# Retrolite_CM4_-_Right_PCB.net
KiCad netlist of a schematic drawn in EAGLE
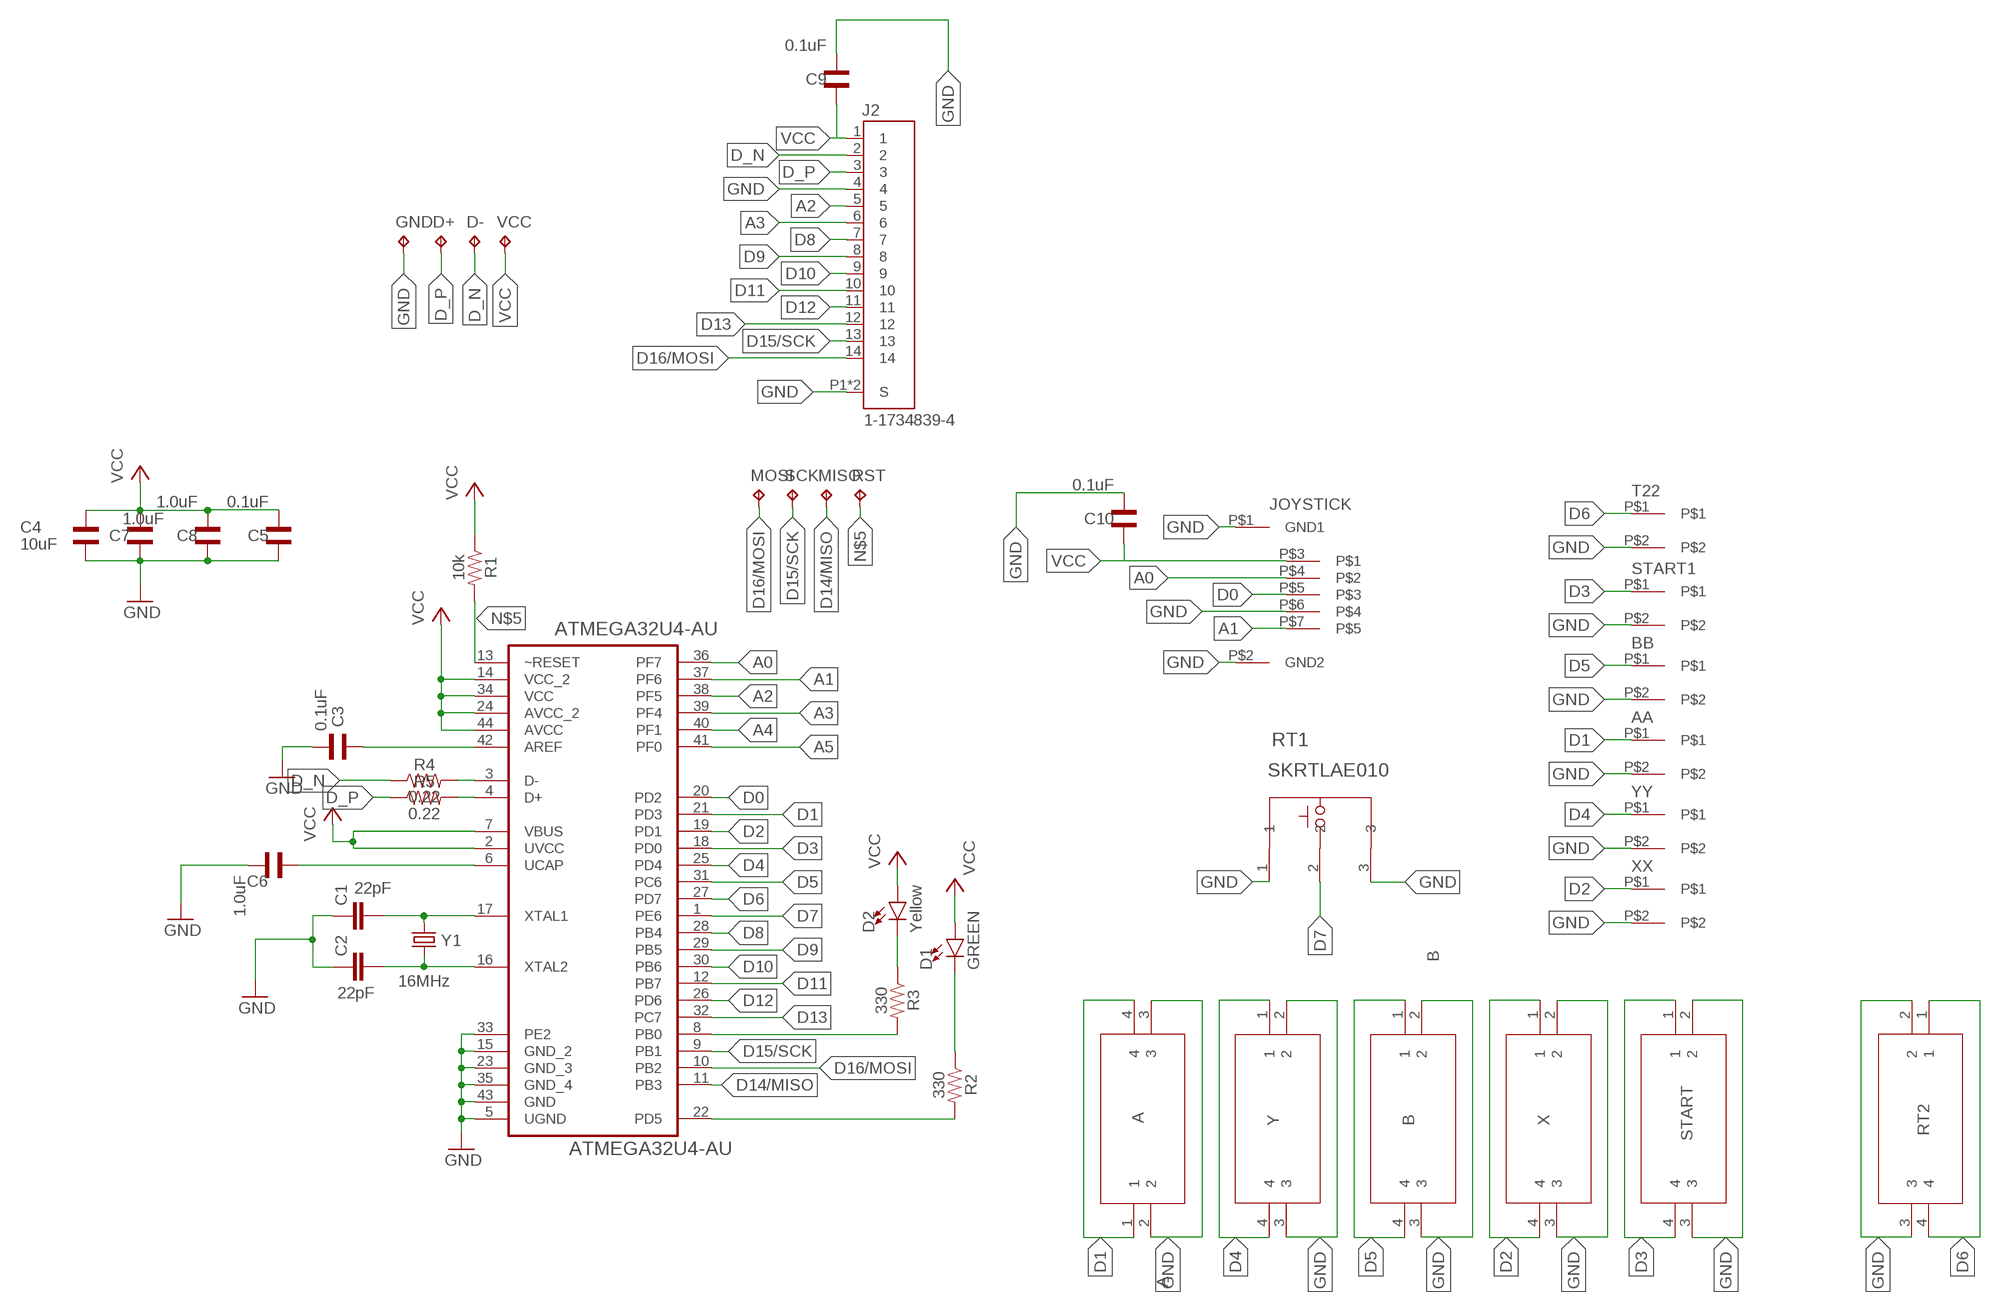
[diagram p0: schematic, sheet 1]

(export (version "E")
  (design (tool "Eeschema 10.0.6"))
  (components
    (comp (ref "A")
      (value "A")
      (footprint "eagle-import:EVQQ2_3")
      (fields (field (name "MF") "Panasonic Electronic") (field (name "MP") "EVQQ2B03W"))
      (libsource (lib "eagle-import") (part "EVQ-Q2B03W"))
    )
    (comp (ref "AA")
      (value "MEMBRANEBUTTON")
      (footprint "eagle-import:MEMBRANEBUTTON")
      (libsource (lib "eagle-import") (part "MEMBRANEBUTTON"))
    )
    (comp (ref "ATMEGA32U4-AU")
      (value "ATMEGA32U4-AU")
      (footprint "eagle-import:QFP80P1200X1200X120-44N")
      (fields (field (name "MF") "Microchip Technology"))
      (libsource (lib "eagle-import") (part "ATMEGA32U4-AU"))
    )
    (comp (ref "B")
      (value "B")
      (footprint "eagle-import:EVQQ2_3")
      (fields (field (name "MF") "Panasonic Electronic") (field (name "MP") "EVQQ2B03W"))
      (libsource (lib "eagle-import") (part "EVQ-Q2B03W"))
    )
    (comp (ref "BB")
      (value "MEMBRANEBUTTON")
      (footprint "eagle-import:MEMBRANEBUTTON")
      (libsource (lib "eagle-import") (part "MEMBRANEBUTTON"))
    )
    (comp (ref "C1")
      (value "22pF")
      (footprint "eagle-import:0603")
      (libsource (lib "eagle-import") (part "22PF-0603-50V-5%"))
    )
    (comp (ref "C2")
      (value "22pF")
      (footprint "eagle-import:0603")
      (libsource (lib "eagle-import") (part "22PF-0603-50V-5%"))
    )
    (comp (ref "C3")
      (value "0.1uF")
      (footprint "eagle-import:WCAP-CSGP_0805_WAVE")
      (libsource (lib "eagle-import") (part "WCAP-CSGP_0805_WAVE_885012006018"))
    )
    (comp (ref "C4")
      (value "10uF")
      (footprint "eagle-import:WCAP-CSGP_0805_WAVE")
      (libsource (lib "eagle-import") (part "WCAP-CSGP_0805_WAVE_885012006018"))
    )
    (comp (ref "C5")
      (value "0.1uF")
      (footprint "eagle-import:WCAP-CSGP_0805_WAVE")
      (libsource (lib "eagle-import") (part "WCAP-CSGP_0805_WAVE_885012006018"))
    )
    (comp (ref "C6")
      (value "1.0uF")
      (footprint "eagle-import:WCAP-CSGP_0805_WAVE")
      (libsource (lib "eagle-import") (part "WCAP-CSGP_0805_WAVE_885012006018"))
    )
    (comp (ref "C7")
      (value "1.0uF")
      (footprint "eagle-import:WCAP-CSGP_0805_WAVE")
      (libsource (lib "eagle-import") (part "WCAP-CSGP_0805_WAVE_885012006018"))
    )
    (comp (ref "C8")
      (value "1.0uF")
      (footprint "eagle-import:WCAP-CSGP_0805_WAVE")
      (libsource (lib "eagle-import") (part "WCAP-CSGP_0805_WAVE_885012006018"))
    )
    (comp (ref "C9")
      (value "0.1uF")
      (footprint "eagle-import:WCAP-CSGP_0805_WAVE")
      (libsource (lib "eagle-import") (part "WCAP-CSGP_0805_WAVE_885012006018"))
    )
    (comp (ref "C10")
      (value "0.1uF")
      (footprint "eagle-import:WCAP-CSGP_0805_WAVE")
      (libsource (lib "eagle-import") (part "WCAP-CSGP_0805_WAVE_885012006018"))
    )
    (comp (ref "D+")
      (value "TPB1,27")
      (footprint "eagle-import:B1,27")
      (libsource (lib "eagle-import") (part "TPB1,27"))
    )
    (comp (ref "D-")
      (value "TPB1,27")
      (footprint "eagle-import:B1,27")
      (libsource (lib "eagle-import") (part "TPB1,27"))
    )
    (comp (ref "D1")
      (value "GREEN")
      (footprint "eagle-import:LED-0603")
      (libsource (lib "eagle-import") (part "LED-GREEN0603"))
    )
    (comp (ref "D2")
      (value "Yellow")
      (footprint "eagle-import:LED-0603")
      (libsource (lib "eagle-import") (part "LED-YELLOW0603"))
    )
    (comp (ref "GND")
      (value "TPB1,27")
      (footprint "eagle-import:B1,27")
      (libsource (lib "eagle-import") (part "TPB1,27"))
    )
    (comp (ref "J2")
      (value "1-1734839-4")
      (footprint "eagle-import:TE_1-1734839-4")
      (fields (field (name "DIGI-KEY_PART_NUMBER") "A100295CT-ND") (field (name "MF") "TE Connectivity"))
      (libsource (lib "eagle-import") (part "1-1734839-4"))
    )
    (comp (ref "JOYSTICK")
      (value "0545500571")
      (footprint "eagle-import:0545500571")
      (libsource (lib "eagle-import") (part "0545500571"))
    )
    (comp (ref "MISO")
      (value "TPB1,27")
      (footprint "eagle-import:B1,27")
      (libsource (lib "eagle-import") (part "TPB1,27"))
    )
    (comp (ref "MOSI")
      (value "TPB1,27")
      (footprint "eagle-import:B1,27")
      (libsource (lib "eagle-import") (part "TPB1,27"))
    )
    (comp (ref "R1")
      (value "10k")
      (footprint "eagle-import:0603")
      (libsource (lib "eagle-import") (part "10KOHM-0603-1/10W-1%"))
    )
    (comp (ref "R2")
      (value "330")
      (footprint "eagle-import:0603")
      (libsource (lib "eagle-import") (part "1.6KOHM-0603-1/10W-1%"))
    )
    (comp (ref "R3")
      (value "330")
      (footprint "eagle-import:0603")
      (libsource (lib "eagle-import") (part "1.6KOHM-0603-1/10W-1%"))
    )
    (comp (ref "R4")
      (value "0.22")
      (footprint "eagle-import:0805")
      (libsource (lib "eagle-import") (part "0.22OHM-0805-1/4W-1%"))
    )
    (comp (ref "R5")
      (value "0.22")
      (footprint "eagle-import:0805")
      (libsource (lib "eagle-import") (part "0.22OHM-0805-1/4W-1%"))
    )
    (comp (ref "RST")
      (value "TPB1,27")
      (footprint "eagle-import:B1,27")
      (libsource (lib "eagle-import") (part "TPB1,27"))
    )
    (comp (ref "RT1")
      (value "SKRTLAE010")
      (footprint "eagle-import:SW3_SKRTLAE010_ALPS")
      (fields (field (name "COPYRIGHT") "Copyright (C) 2016 Accelerated Designs. All rights reserved"))
      (libsource (lib "eagle-import") (part "SKRTLAE010"))
    )
    (comp (ref "RT2")
      (value "T2")
      (footprint "eagle-import:EVQQ2_3")
      (fields (field (name "MF") "Panasonic Electronic") (field (name "MP") "EVQQ2B03W"))
      (libsource (lib "eagle-import") (part "EVQ-Q2B03W"))
    )
    (comp (ref "SCK")
      (value "TPB1,27")
      (footprint "eagle-import:B1,27")
      (libsource (lib "eagle-import") (part "TPB1,27"))
    )
    (comp (ref "START")
      (value "START")
      (footprint "eagle-import:EVQQ2_3")
      (fields (field (name "MF") "Panasonic Electronic") (field (name "MP") "EVQQ2B03W"))
      (libsource (lib "eagle-import") (part "EVQ-Q2B03W"))
    )
    (comp (ref "START1")
      (value "MEMBRANEBUTTON")
      (footprint "eagle-import:MEMBRANEBUTTON")
      (libsource (lib "eagle-import") (part "MEMBRANEBUTTON"))
    )
    (comp (ref "T22")
      (value "MEMBRANEBUTTON")
      (footprint "eagle-import:MEMBRANEBUTTON")
      (libsource (lib "eagle-import") (part "MEMBRANEBUTTON"))
    )
    (comp (ref "VCC")
      (value "TPB1,27")
      (footprint "eagle-import:B1,27")
      (libsource (lib "eagle-import") (part "TPB1,27"))
    )
    (comp (ref "X")
      (value "X")
      (footprint "eagle-import:EVQQ2_3")
      (fields (field (name "MF") "Panasonic Electronic") (field (name "MP") "EVQQ2B03W"))
      (libsource (lib "eagle-import") (part "EVQ-Q2B03W"))
    )
    (comp (ref "XX")
      (value "MEMBRANEBUTTON")
      (footprint "eagle-import:MEMBRANEBUTTON")
      (libsource (lib "eagle-import") (part "MEMBRANEBUTTON"))
    )
    (comp (ref "Y")
      (value "Y")
      (footprint "eagle-import:EVQQ2_3")
      (fields (field (name "MF") "Panasonic Electronic") (field (name "MP") "EVQQ2B03W"))
      (libsource (lib "eagle-import") (part "EVQ-Q2B03W"))
    )
    (comp (ref "Y1")
      (value "16MHz")
      (footprint "eagle-import:CRYSTAL-SMD-5X3.2-4PAD")
      (libsource (lib "eagle-import") (part "CRYSTAL-16MHZSMD-5X3.2"))
    )
    (comp (ref "YY")
      (value "MEMBRANEBUTTON")
      (footprint "eagle-import:MEMBRANEBUTTON")
      (libsource (lib "eagle-import") (part "MEMBRANEBUTTON"))
    )
  )
  (nets
    (net (code "1") (name "A0") (class "Default")
      (node (ref "ATMEGA32U4-AU") (pin "36") (pinfunction "PF7_36") (pintype "bidirectional"))
      (node (ref "JOYSTICK") (pin "P$4") (pinfunction "P$2_P$4") (pintype "bidirectional"))
    )
    (net (code "2") (name "A1") (class "Default")
      (node (ref "ATMEGA32U4-AU") (pin "37") (pinfunction "PF6_37") (pintype "bidirectional"))
      (node (ref "JOYSTICK") (pin "P$7") (pinfunction "P$5_P$7") (pintype "bidirectional"))
    )
    (net (code "3") (name "A2") (class "Default")
      (node (ref "ATMEGA32U4-AU") (pin "38") (pinfunction "PF5_38") (pintype "bidirectional"))
      (node (ref "J2") (pin "5") (pinfunction "5_5") (pintype "passive"))
    )
    (net (code "4") (name "A3") (class "Default")
      (node (ref "ATMEGA32U4-AU") (pin "39") (pinfunction "PF4_39") (pintype "bidirectional"))
      (node (ref "J2") (pin "6") (pinfunction "6_6") (pintype "passive"))
    )
    (net (code "5") (name "A4") (class "Default")
      (node (ref "ATMEGA32U4-AU") (pin "40") (pinfunction "PF1_40") (pintype "bidirectional"))
    )
    (net (code "6") (name "A5") (class "Default")
      (node (ref "ATMEGA32U4-AU") (pin "41") (pinfunction "PF0_41") (pintype "bidirectional"))
    )
    (net (code "7") (name "D0") (class "Default")
      (node (ref "ATMEGA32U4-AU") (pin "20") (pinfunction "PD2_20") (pintype "bidirectional"))
      (node (ref "JOYSTICK") (pin "P$5") (pinfunction "P$3_P$5") (pintype "bidirectional"))
    )
    (net (code "8") (name "D1") (class "Default")
      (node (ref "A") (pin "1") (pinfunction "1_1") (pintype "passive"))
      (node (ref "A") (pin "4") (pinfunction "4_4") (pintype "passive"))
      (node (ref "AA") (pin "P$1") (pinfunction "P$1_P$1") (pintype "bidirectional"))
      (node (ref "ATMEGA32U4-AU") (pin "21") (pinfunction "PD3_21") (pintype "bidirectional"))
    )
    (net (code "9") (name "D2") (class "Default")
      (node (ref "ATMEGA32U4-AU") (pin "19") (pinfunction "PD1_19") (pintype "bidirectional"))
      (node (ref "X") (pin "1") (pinfunction "1_1") (pintype "passive"))
      (node (ref "X") (pin "4") (pinfunction "4_4") (pintype "passive"))
      (node (ref "XX") (pin "P$1") (pinfunction "P$1_P$1") (pintype "bidirectional"))
    )
    (net (code "10") (name "D3") (class "Default")
      (node (ref "ATMEGA32U4-AU") (pin "18") (pinfunction "PD0_18") (pintype "bidirectional"))
      (node (ref "START") (pin "1") (pinfunction "1_1") (pintype "passive"))
      (node (ref "START") (pin "4") (pinfunction "4_4") (pintype "passive"))
      (node (ref "START1") (pin "P$1") (pinfunction "P$1_P$1") (pintype "bidirectional"))
    )
    (net (code "11") (name "D4") (class "Default")
      (node (ref "ATMEGA32U4-AU") (pin "25") (pinfunction "PD4_25") (pintype "bidirectional"))
      (node (ref "Y") (pin "1") (pinfunction "1_1") (pintype "passive"))
      (node (ref "Y") (pin "4") (pinfunction "4_4") (pintype "passive"))
      (node (ref "YY") (pin "P$1") (pinfunction "P$1_P$1") (pintype "bidirectional"))
    )
    (net (code "12") (name "D5") (class "Default")
      (node (ref "ATMEGA32U4-AU") (pin "31") (pinfunction "PC6_31") (pintype "bidirectional"))
      (node (ref "B") (pin "1") (pinfunction "1_1") (pintype "passive"))
      (node (ref "B") (pin "4") (pinfunction "4_4") (pintype "passive"))
      (node (ref "BB") (pin "P$1") (pinfunction "P$1_P$1") (pintype "bidirectional"))
    )
    (net (code "13") (name "D6") (class "Default")
      (node (ref "ATMEGA32U4-AU") (pin "27") (pinfunction "PD7_27") (pintype "bidirectional"))
      (node (ref "RT2") (pin "1") (pinfunction "1_1") (pintype "passive"))
      (node (ref "RT2") (pin "4") (pinfunction "4_4") (pintype "passive"))
      (node (ref "T22") (pin "P$1") (pinfunction "P$1_P$1") (pintype "bidirectional"))
    )
    (net (code "14") (name "D7") (class "Default")
      (node (ref "ATMEGA32U4-AU") (pin "1") (pinfunction "PE6_1") (pintype "bidirectional"))
      (node (ref "RT1") (pin "2") (pinfunction "2_2") (pintype "passive"))
    )
    (net (code "15") (name "D8") (class "Default")
      (node (ref "ATMEGA32U4-AU") (pin "28") (pinfunction "PB4_28") (pintype "bidirectional"))
      (node (ref "J2") (pin "7") (pinfunction "7_7") (pintype "passive"))
    )
    (net (code "16") (name "D9") (class "Default")
      (node (ref "ATMEGA32U4-AU") (pin "29") (pinfunction "PB5_29") (pintype "bidirectional"))
      (node (ref "J2") (pin "8") (pinfunction "8_8") (pintype "passive"))
    )
    (net (code "17") (name "D10") (class "Default")
      (node (ref "ATMEGA32U4-AU") (pin "30") (pinfunction "PB6_30") (pintype "bidirectional"))
      (node (ref "J2") (pin "9") (pinfunction "9_9") (pintype "passive"))
    )
    (net (code "18") (name "D11") (class "Default")
      (node (ref "ATMEGA32U4-AU") (pin "12") (pinfunction "PB7_12") (pintype "bidirectional"))
      (node (ref "J2") (pin "10") (pinfunction "10_10") (pintype "passive"))
    )
    (net (code "19") (name "D12") (class "Default")
      (node (ref "ATMEGA32U4-AU") (pin "26") (pinfunction "PD6_26") (pintype "bidirectional"))
      (node (ref "J2") (pin "11") (pinfunction "11_11") (pintype "passive"))
    )
    (net (code "20") (name "D13") (class "Default")
      (node (ref "ATMEGA32U4-AU") (pin "32") (pinfunction "PC7_32") (pintype "bidirectional"))
      (node (ref "J2") (pin "12") (pinfunction "12_12") (pintype "passive"))
    )
    (net (code "21") (name "D14{slash}MISO") (class "Default")
      (node (ref "ATMEGA32U4-AU") (pin "11") (pinfunction "PB3_11") (pintype "bidirectional"))
      (node (ref "MISO") (pin "TP") (pinfunction "TP_TP") (pintype "input"))
    )
    (net (code "22") (name "D15{slash}SCK") (class "Default")
      (node (ref "ATMEGA32U4-AU") (pin "9") (pinfunction "PB1_9") (pintype "bidirectional"))
      (node (ref "J2") (pin "13") (pinfunction "13_13") (pintype "passive"))
      (node (ref "SCK") (pin "TP") (pinfunction "TP_TP") (pintype "input"))
    )
    (net (code "23") (name "D16{slash}MOSI") (class "Default")
      (node (ref "ATMEGA32U4-AU") (pin "10") (pinfunction "PB2_10") (pintype "bidirectional"))
      (node (ref "J2") (pin "14") (pinfunction "14_14") (pintype "passive"))
      (node (ref "MOSI") (pin "TP") (pinfunction "TP_TP") (pintype "input"))
    )
    (net (code "24") (name "D_N") (class "Default")
      (node (ref "D-") (pin "TP") (pinfunction "TP_TP") (pintype "input"))
      (node (ref "J2") (pin "2") (pinfunction "2_2") (pintype "passive"))
      (node (ref "R4") (pin "1") (pinfunction "1_1") (pintype "passive"))
    )
    (net (code "25") (name "D_P") (class "Default")
      (node (ref "D+") (pin "TP") (pinfunction "TP_TP") (pintype "input"))
      (node (ref "J2") (pin "3") (pinfunction "3_3") (pintype "passive"))
      (node (ref "R5") (pin "1") (pinfunction "1_1") (pintype "passive"))
    )
    (net (code "26") (name "GND") (class "Default")
      (node (ref "A") (pin "2") (pinfunction "2_2") (pintype "passive"))
      (node (ref "A") (pin "3") (pinfunction "3_3") (pintype "passive"))
      (node (ref "AA") (pin "P$2") (pinfunction "P$2_P$2") (pintype "bidirectional"))
      (node (ref "ATMEGA32U4-AU") (pin "15") (pinfunction "GND_2_15") (pintype "passive"))
      (node (ref "ATMEGA32U4-AU") (pin "23") (pinfunction "GND_3_23") (pintype "passive"))
      (node (ref "ATMEGA32U4-AU") (pin "33") (pinfunction "PE2_33") (pintype "bidirectional"))
      (node (ref "ATMEGA32U4-AU") (pin "35") (pinfunction "GND_4_35") (pintype "passive"))
      (node (ref "ATMEGA32U4-AU") (pin "43") (pinfunction "GND_43") (pintype "passive"))
      (node (ref "ATMEGA32U4-AU") (pin "5") (pinfunction "UGND_5") (pintype "passive"))
      (node (ref "B") (pin "2") (pinfunction "2_2") (pintype "passive"))
      (node (ref "B") (pin "3") (pinfunction "3_3") (pintype "passive"))
      (node (ref "BB") (pin "P$2") (pinfunction "P$2_P$2") (pintype "bidirectional"))
      (node (ref "C1") (pin "1") (pinfunction "1_1") (pintype "passive"))
      (node (ref "C10") (pin "1") (pinfunction "1_1") (pintype "passive"))
      (node (ref "C2") (pin "1") (pinfunction "1_1") (pintype "passive"))
      (node (ref "C3") (pin "1") (pinfunction "1_1") (pintype "passive"))
      (node (ref "C4") (pin "1") (pinfunction "1_1") (pintype "passive"))
      (node (ref "C5") (pin "2") (pinfunction "2_2") (pintype "passive"))
      (node (ref "C6") (pin "1") (pinfunction "1_1") (pintype "passive"))
      (node (ref "C7") (pin "2") (pinfunction "2_2") (pintype "passive"))
      (node (ref "C8") (pin "2") (pinfunction "2_2") (pintype "passive"))
      (node (ref "C9") (pin "1") (pinfunction "1_1") (pintype "passive"))
      (node (ref "GND") (pin "TP") (pinfunction "TP_TP") (pintype "input"))
      (node (ref "J2") (pin "4") (pinfunction "4_4") (pintype "passive"))
      (node (ref "J2") (pin "P1") (pinfunction "S_P1") (pintype "passive"))
      (node (ref "J2") (pin "P2") (pinfunction "S_P2") (pintype "passive"))
      (node (ref "JOYSTICK") (pin "P$1") (pinfunction "GND1_P$1") (pintype "bidirectional"))
      (node (ref "JOYSTICK") (pin "P$2") (pinfunction "GND2_P$2") (pintype "bidirectional"))
      (node (ref "JOYSTICK") (pin "P$6") (pinfunction "P$4_P$6") (pintype "bidirectional"))
      (node (ref "RT1") (pin "1") (pinfunction "1_1") (pintype "passive"))
      (node (ref "RT1") (pin "3") (pinfunction "3_3") (pintype "passive"))
      (node (ref "RT2") (pin "2") (pinfunction "2_2") (pintype "passive"))
      (node (ref "RT2") (pin "3") (pinfunction "3_3") (pintype "passive"))
      (node (ref "START") (pin "2") (pinfunction "2_2") (pintype "passive"))
      (node (ref "START") (pin "3") (pinfunction "3_3") (pintype "passive"))
      (node (ref "START1") (pin "P$2") (pinfunction "P$2_P$2") (pintype "bidirectional"))
      (node (ref "T22") (pin "P$2") (pinfunction "P$2_P$2") (pintype "bidirectional"))
      (node (ref "X") (pin "2") (pinfunction "2_2") (pintype "passive"))
      (node (ref "X") (pin "3") (pinfunction "3_3") (pintype "passive"))
      (node (ref "XX") (pin "P$2") (pinfunction "P$2_P$2") (pintype "bidirectional"))
      (node (ref "Y") (pin "2") (pinfunction "2_2") (pintype "passive"))
      (node (ref "Y") (pin "3") (pinfunction "3_3") (pintype "passive"))
      (node (ref "YY") (pin "P$2") (pinfunction "P$2_P$2") (pintype "bidirectional"))
    )
    (net (code "27") (name "N$5") (class "Default")
      (node (ref "ATMEGA32U4-AU") (pin "13") (pinfunction "~{RESET}_13") (pintype "input"))
      (node (ref "R1") (pin "2") (pinfunction "2_2") (pintype "passive"))
      (node (ref "RST") (pin "TP") (pinfunction "TP_TP") (pintype "input"))
    )
    (net (code "28") (name "Net-(ATMEGA32U4-AU-AREF)") (class "Default")
      (node (ref "ATMEGA32U4-AU") (pin "42") (pinfunction "AREF_42") (pintype "input"))
      (node (ref "C3") (pin "2") (pinfunction "2_2") (pintype "passive"))
    )
    (net (code "29") (name "Net-(ATMEGA32U4-AU-D+)") (class "Default")
      (node (ref "ATMEGA32U4-AU") (pin "4") (pinfunction "D+_4") (pintype "passive"))
      (node (ref "R5") (pin "2") (pinfunction "2_2") (pintype "passive"))
    )
    (net (code "30") (name "Net-(ATMEGA32U4-AU-D-)") (class "Default")
      (node (ref "ATMEGA32U4-AU") (pin "3") (pinfunction "D-_3") (pintype "passive"))
      (node (ref "R4") (pin "2") (pinfunction "2_2") (pintype "passive"))
    )
    (net (code "31") (name "Net-(ATMEGA32U4-AU-PB0)") (class "Default")
      (node (ref "ATMEGA32U4-AU") (pin "8") (pinfunction "PB0_8") (pintype "bidirectional"))
      (node (ref "R3") (pin "2") (pinfunction "2_2") (pintype "passive"))
    )
    (net (code "32") (name "Net-(ATMEGA32U4-AU-PD5)") (class "Default")
      (node (ref "ATMEGA32U4-AU") (pin "22") (pinfunction "PD5_22") (pintype "bidirectional"))
      (node (ref "R2") (pin "2") (pinfunction "2_2") (pintype "passive"))
    )
    (net (code "33") (name "Net-(ATMEGA32U4-AU-UCAP)") (class "Default")
      (node (ref "ATMEGA32U4-AU") (pin "6") (pinfunction "UCAP_6") (pintype "power_in"))
      (node (ref "C6") (pin "2") (pinfunction "2_2") (pintype "passive"))
    )
    (net (code "34") (name "Net-(ATMEGA32U4-AU-XTAL1)") (class "Default")
      (node (ref "ATMEGA32U4-AU") (pin "17") (pinfunction "XTAL1_17") (pintype "input"))
      (node (ref "C1") (pin "2") (pinfunction "2_2") (pintype "passive"))
      (node (ref "Y1") (pin "1") (pinfunction "1_1") (pintype "passive"))
    )
    (net (code "35") (name "Net-(ATMEGA32U4-AU-XTAL2)") (class "Default")
      (node (ref "ATMEGA32U4-AU") (pin "16") (pinfunction "XTAL2_16") (pintype "output"))
      (node (ref "C2") (pin "2") (pinfunction "2_2") (pintype "passive"))
      (node (ref "Y1") (pin "3") (pinfunction "2_3") (pintype "passive"))
    )
    (net (code "36") (name "Net-(D1-PadC)") (class "Default")
      (node (ref "D1") (pin "C") (pinfunction "C_C") (pintype "passive"))
      (node (ref "R2") (pin "1") (pinfunction "1_1") (pintype "passive"))
    )
    (net (code "37") (name "Net-(D2-PadC)") (class "Default")
      (node (ref "D2") (pin "C") (pinfunction "C_C") (pintype "passive"))
      (node (ref "R3") (pin "1") (pinfunction "1_1") (pintype "passive"))
    )
    (net (code "38") (name "VCC") (class "Default")
      (node (ref "ATMEGA32U4-AU") (pin "14") (pinfunction "VCC_2_14") (pintype "power_in"))
      (node (ref "ATMEGA32U4-AU") (pin "2") (pinfunction "UVCC_2") (pintype "power_in"))
      (node (ref "ATMEGA32U4-AU") (pin "24") (pinfunction "AVCC_2_24") (pintype "power_in"))
      (node (ref "ATMEGA32U4-AU") (pin "34") (pinfunction "VCC_34") (pintype "power_in"))
      (node (ref "ATMEGA32U4-AU") (pin "44") (pinfunction "AVCC_44") (pintype "power_in"))
      (node (ref "ATMEGA32U4-AU") (pin "7") (pinfunction "VBUS_7") (pintype "input"))
      (node (ref "C10") (pin "2") (pinfunction "2_2") (pintype "passive"))
      (node (ref "C4") (pin "2") (pinfunction "2_2") (pintype "passive"))
      (node (ref "C5") (pin "1") (pinfunction "1_1") (pintype "passive"))
      (node (ref "C7") (pin "1") (pinfunction "1_1") (pintype "passive"))
      (node (ref "C8") (pin "1") (pinfunction "1_1") (pintype "passive"))
      (node (ref "C9") (pin "2") (pinfunction "2_2") (pintype "passive"))
      (node (ref "D1") (pin "A") (pinfunction "A_A") (pintype "passive"))
      (node (ref "D2") (pin "A") (pinfunction "A_A") (pintype "passive"))
      (node (ref "J2") (pin "1") (pinfunction "1_1") (pintype "passive"))
      (node (ref "JOYSTICK") (pin "P$3") (pinfunction "P$1_P$3") (pintype "bidirectional"))
      (node (ref "R1") (pin "1") (pinfunction "1_1") (pintype "passive"))
      (node (ref "VCC") (pin "TP") (pinfunction "TP_TP") (pintype "input"))
    )
  )
)
